# mosfet.net
KiCad netlist of a schematic drawn in Altium Designer
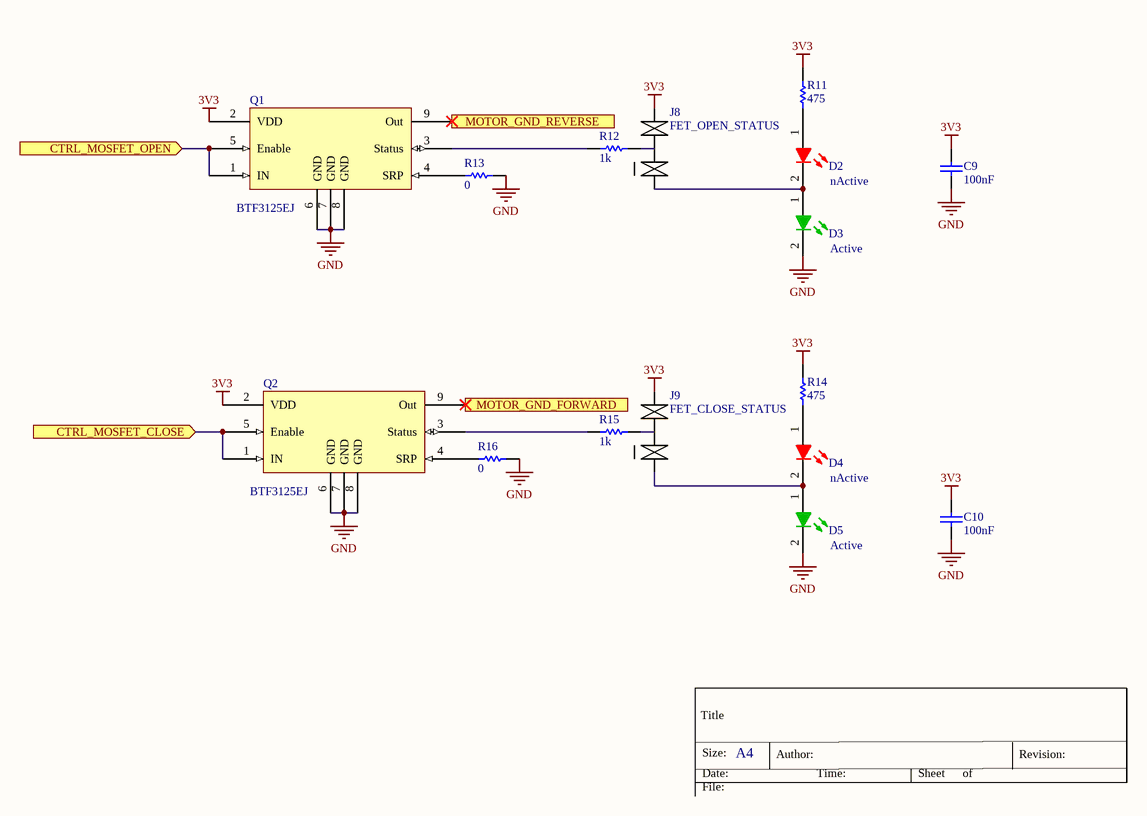
[diagram p0: mosfet.SchDoc]

(export (version "E")
  (design (tool "Eeschema 10.0.6"))
  (components
    (comp (ref "C9")
      (value "100nF")
      (footprint "CAP0603")
      (description "Chip Capacitor 0603, Body 1.6x0.8mm, IPC Medium Density")
      (libsource (lib "capacitors") (part "Capacitor 0603"))
    )
    (comp (ref "C10")
      (value "100nF")
      (footprint "CAP0603")
      (description "Chip Capacitor 0603, Body 1.6x0.8mm, IPC Medium Density")
      (libsource (lib "capacitors") (part "Capacitor 0603"))
    )
    (comp (ref "D2")
      (value "nActive")
      (footprint "0603 LED Red")
      (description "LED, SMT, 0603(1608), 1.1mm thickness, Red")
      (libsource (lib "diodes") (part "LED Red 0603"))
    )
    (comp (ref "D3")
      (value "Active")
      (footprint "0603 LED Green")
      (description "LED, SMT, 0603(1608), 1.1mm thickness, Green")
      (libsource (lib "diodes") (part "LED Green 0603"))
    )
    (comp (ref "D4")
      (value "nActive")
      (footprint "0603 LED Red")
      (description "LED, SMT, 0603(1608), 1.1mm thickness, Red")
      (libsource (lib "diodes") (part "LED Red 0603"))
    )
    (comp (ref "D5")
      (value "Active")
      (footprint "0603 LED Green")
      (description "LED, SMT, 0603(1608), 1.1mm thickness, Green")
      (libsource (lib "diodes") (part "LED Green 0603"))
    )
    (comp (ref "J8")
      (value "FET_OPEN_STATUS")
      (footprint "Jumper Dual")
      (description "Jumper Dual")
      (libsource (lib "miscellaneous") (part "Jumper Dual"))
    )
    (comp (ref "J9")
      (value "FET_CLOSE_STATUS")
      (footprint "Jumper Dual")
      (description "Jumper Dual")
      (libsource (lib "miscellaneous") (part "Jumper Dual"))
    )
    (comp (ref "Q1")
      (value "BTF3125EJ")
      (footprint "BTF3xxxEJ")
      (description "BTF3125EJ is a 125 mΩ single channel Smart Low-Side Power Switch")
      (libsource (lib "ic_power") (part "BTF3125EJ"))
    )
    (comp (ref "Q2")
      (value "BTF3125EJ")
      (footprint "BTF3xxxEJ")
      (description "BTF3125EJ is a 125 mΩ single channel Smart Low-Side Power Switch")
      (libsource (lib "ic_power") (part "BTF3125EJ"))
    )
    (comp (ref "R11")
      (value "475")
      (footprint "RES0603")
      (description "Chip Resistor 0603, Body 1.6x0.8mm, IPC Medium Density")
      (libsource (lib "resistors") (part "Resistor 0603"))
    )
    (comp (ref "R12")
      (value "1k")
      (footprint "RES0603")
      (description "Chip Resistor 0603, Body 1.6x0.8mm, IPC Medium Density")
      (libsource (lib "resistors") (part "Resistor 0603"))
    )
    (comp (ref "R13")
      (value "0")
      (footprint "RES0603")
      (description "Chip Resistor 0603, Body 1.6x0.8mm, IPC Medium Density")
      (libsource (lib "resistors") (part "Resistor 0603"))
    )
    (comp (ref "R14")
      (value "475")
      (footprint "RES0603")
      (description "Chip Resistor 0603, Body 1.6x0.8mm, IPC Medium Density")
      (libsource (lib "resistors") (part "Resistor 0603"))
    )
    (comp (ref "R15")
      (value "1k")
      (footprint "RES0603")
      (description "Chip Resistor 0603, Body 1.6x0.8mm, IPC Medium Density")
      (libsource (lib "resistors") (part "Resistor 0603"))
    )
    (comp (ref "R16")
      (value "0")
      (footprint "RES0603")
      (description "Chip Resistor 0603, Body 1.6x0.8mm, IPC Medium Density")
      (libsource (lib "resistors") (part "Resistor 0603"))
    )
  )
  (nets
    (net (code "1") (name "/CTRL_MOSFET_CLOSE") (class "Default")
      (node (ref "Q2") (pin "1") (pinfunction "IN_1") (pintype "input"))
      (node (ref "Q2") (pin "5") (pinfunction "Enable_5") (pintype "input"))
    )
    (net (code "2") (name "/CTRL_MOSFET_OPEN") (class "Default")
      (node (ref "Q1") (pin "1") (pinfunction "IN_1") (pintype "input"))
      (node (ref "Q1") (pin "5") (pinfunction "Enable_5") (pintype "input"))
    )
    (net (code "3") (name "/MOTOR_GND_FORWARD") (class "Default")
      (node (ref "Q2") (pin "9") (pinfunction "Out_9") (pintype "power_in+no_connect"))
    )
    (net (code "4") (name "/MOTOR_GND_REVERSE") (class "Default")
      (node (ref "Q1") (pin "9") (pinfunction "Out_9") (pintype "power_in+no_connect"))
    )
    (net (code "5") (name "3V3") (class "Default")
      (node (ref "C10") (pin "2") (pinfunction "2_2") (pintype "passive"))
      (node (ref "C9") (pin "2") (pinfunction "2_2") (pintype "passive"))
      (node (ref "J8") (pin "2") (pinfunction "B_2") (pintype "passive"))
      (node (ref "J9") (pin "2") (pinfunction "B_2") (pintype "passive"))
      (node (ref "Q1") (pin "2") (pinfunction "VDD_2") (pintype "power_in"))
      (node (ref "Q2") (pin "2") (pinfunction "VDD_2") (pintype "power_in"))
      (node (ref "R11") (pin "2") (pinfunction "2_2") (pintype "passive"))
      (node (ref "R14") (pin "2") (pinfunction "2_2") (pintype "passive"))
    )
    (net (code "6") (name "GND") (class "Default")
      (node (ref "C10") (pin "1") (pinfunction "1_1") (pintype "passive"))
      (node (ref "C9") (pin "1") (pinfunction "1_1") (pintype "passive"))
      (node (ref "D3") (pin "2") (pinfunction "K_2") (pintype "passive"))
      (node (ref "D5") (pin "2") (pinfunction "K_2") (pintype "passive"))
      (node (ref "Q1") (pin "6") (pinfunction "GND_6") (pintype "power_in"))
      (node (ref "Q1") (pin "7") (pinfunction "GND_7") (pintype "power_in"))
      (node (ref "Q1") (pin "8") (pinfunction "GND_8") (pintype "power_in"))
      (node (ref "Q2") (pin "6") (pinfunction "GND_6") (pintype "power_in"))
      (node (ref "Q2") (pin "7") (pinfunction "GND_7") (pintype "power_in"))
      (node (ref "Q2") (pin "8") (pinfunction "GND_8") (pintype "power_in"))
      (node (ref "R13") (pin "2") (pinfunction "2_2") (pintype "passive"))
      (node (ref "R16") (pin "2") (pinfunction "2_2") (pintype "passive"))
    )
    (net (code "7") (name "Net-(D2-A)") (class "Default")
      (node (ref "D2") (pin "1") (pinfunction "A_1") (pintype "passive"))
      (node (ref "R11") (pin "1") (pinfunction "1_1") (pintype "passive"))
    )
    (net (code "8") (name "Net-(D2-K)") (class "Default")
      (node (ref "D2") (pin "2") (pinfunction "K_2") (pintype "passive"))
      (node (ref "D3") (pin "1") (pinfunction "A_1") (pintype "passive"))
      (node (ref "J8") (pin "1") (pinfunction "A_1") (pintype "passive"))
    )
    (net (code "9") (name "Net-(D4-A)") (class "Default")
      (node (ref "D4") (pin "1") (pinfunction "A_1") (pintype "passive"))
      (node (ref "R14") (pin "1") (pinfunction "1_1") (pintype "passive"))
    )
    (net (code "10") (name "Net-(D4-K)") (class "Default")
      (node (ref "D4") (pin "2") (pinfunction "K_2") (pintype "passive"))
      (node (ref "D5") (pin "1") (pinfunction "A_1") (pintype "passive"))
      (node (ref "J9") (pin "1") (pinfunction "A_1") (pintype "passive"))
    )
    (net (code "11") (name "Net-(J8-C)") (class "Default")
      (node (ref "J8") (pin "3") (pinfunction "C_3") (pintype "passive"))
      (node (ref "R12") (pin "2") (pinfunction "2_2") (pintype "passive"))
    )
    (net (code "12") (name "Net-(J9-C)") (class "Default")
      (node (ref "J9") (pin "3") (pinfunction "C_3") (pintype "passive"))
      (node (ref "R15") (pin "2") (pinfunction "2_2") (pintype "passive"))
    )
    (net (code "13") (name "Net-(Q1-SRP)") (class "Default")
      (node (ref "Q1") (pin "4") (pinfunction "SRP_4") (pintype "input"))
      (node (ref "R13") (pin "1") (pinfunction "1_1") (pintype "passive"))
    )
    (net (code "14") (name "Net-(Q1-Status)") (class "Default")
      (node (ref "Q1") (pin "3") (pinfunction "Status_3") (pintype "bidirectional"))
      (node (ref "R12") (pin "1") (pinfunction "1_1") (pintype "passive"))
    )
    (net (code "15") (name "Net-(Q2-SRP)") (class "Default")
      (node (ref "Q2") (pin "4") (pinfunction "SRP_4") (pintype "input"))
      (node (ref "R16") (pin "1") (pinfunction "1_1") (pintype "passive"))
    )
    (net (code "16") (name "Net-(Q2-Status)") (class "Default")
      (node (ref "Q2") (pin "3") (pinfunction "Status_3") (pintype "bidirectional"))
      (node (ref "R15") (pin "1") (pinfunction "1_1") (pintype "passive"))
    )
  )
)
